# Others.net
KiCad netlist of a schematic drawn in Altium Designer
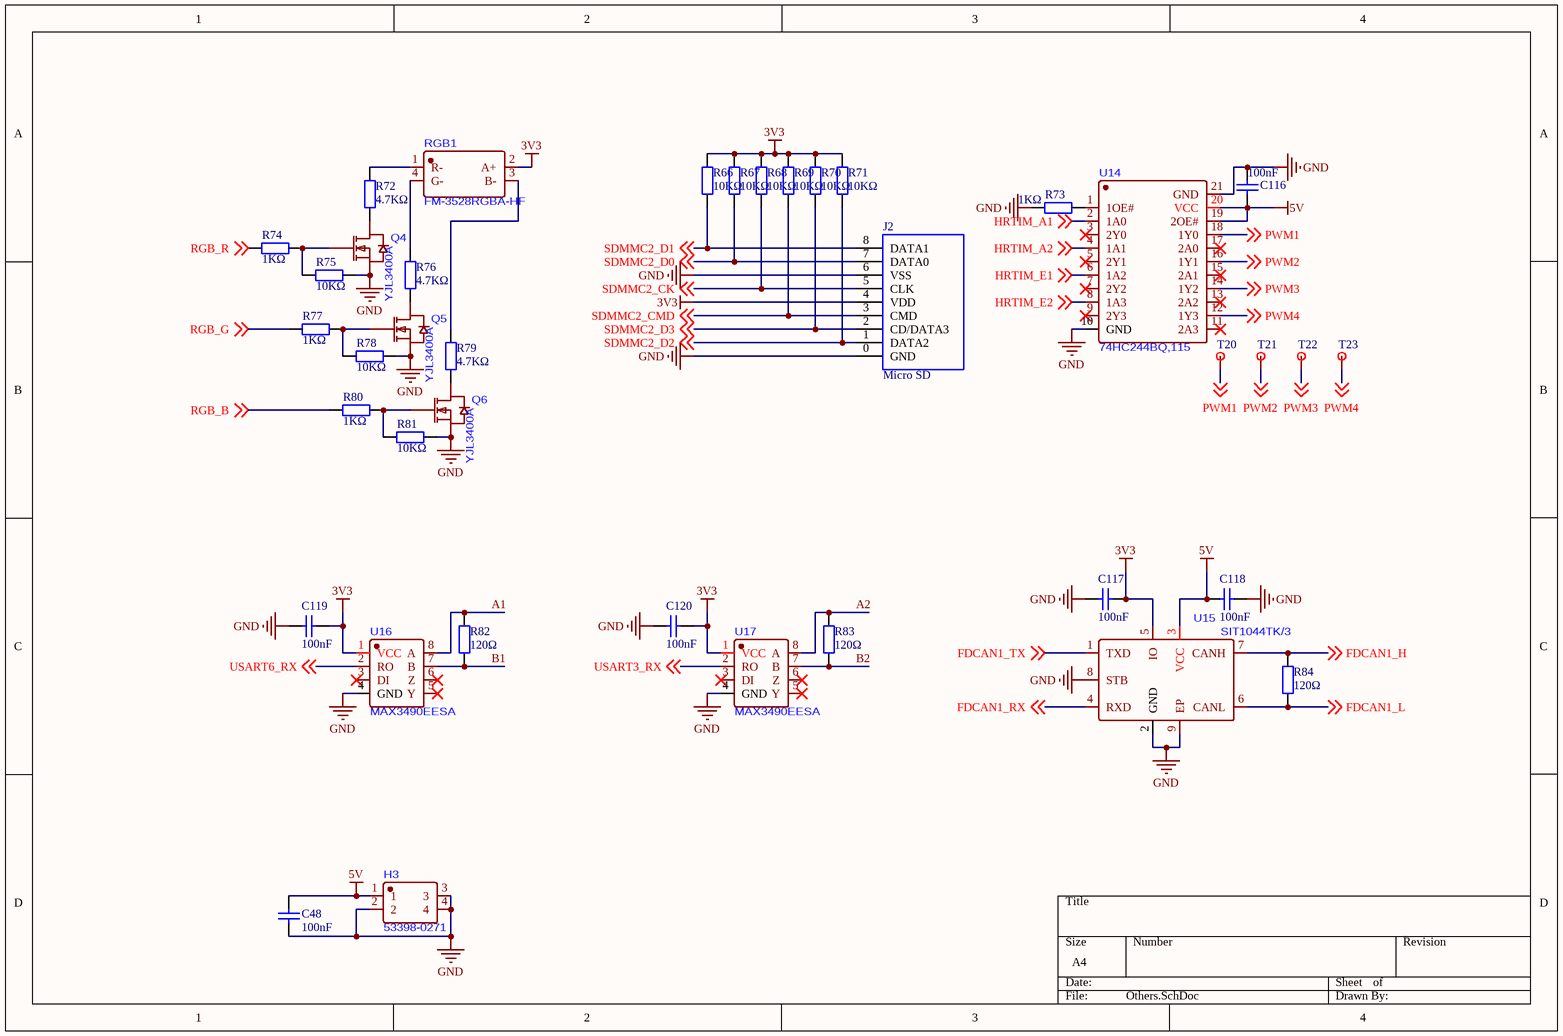
[diagram p0: Others.SchDoc]

(export (version "E")
  (design (tool "Eeschema 10.0.6"))
  (components
    (comp (ref "C48")
      (value "100nF")
      (footprint "0402_C")
      (description "贴片电容")
      (libsource (lib "Miscellaneous Devices LC") (part "0402 100nF (104) 10% 16V"))
    )
    (comp (ref "C116")
      (value "100nF")
      (footprint "0402_C")
      (description "贴片电容")
      (libsource (lib "Miscellaneous Devices LC") (part "0402 100nF (104) 10% 16V"))
    )
    (comp (ref "C117")
      (value "100nF")
      (footprint "0402_C")
      (description "贴片电容")
      (libsource (lib "Miscellaneous Devices LC") (part "0402 100nF (104) 10% 16V"))
    )
    (comp (ref "C118")
      (value "100nF")
      (footprint "0402_C")
      (description "贴片电容")
      (libsource (lib "Miscellaneous Devices LC") (part "0402 100nF (104) 10% 16V"))
    )
    (comp (ref "C119")
      (value "100nF")
      (footprint "0402_C")
      (description "贴片电容")
      (libsource (lib "Miscellaneous Devices LC") (part "0402 100nF (104) 10% 16V"))
    )
    (comp (ref "C120")
      (value "100nF")
      (footprint "0402_C")
      (description "贴片电容")
      (libsource (lib "Miscellaneous Devices LC") (part "0402 100nF (104) 10% 16V"))
    )
    (comp (ref "H3")
      (value "53398-0271")
      (footprint "CONN-SMD_2P-P1.25_53398-0271")
      (libsource (lib "JiangCi") (part "53398-0271"))
    )
    (comp (ref "J2")
      (value "Micro SD")
      (footprint "SD卡座短")
      (description "Micro SD卡")
      (fields (field (name "版权归属") "黎明电子style"))
      (libsource (lib "RM2020原理图库v1.3 (1)") (part "SD卡 短"))
    )
    (comp (ref "Q4")
      (value "YJL3400A")
      (footprint "SOT-23-3_L2.9-W1.3-P1.90-LS2.4-BR")
      (libsource (lib "JiangCi") (part "YJL3400A"))
    )
    (comp (ref "Q5")
      (value "YJL3400A")
      (footprint "SOT-23-3_L2.9-W1.3-P1.90-LS2.4-BR")
      (libsource (lib "JiangCi") (part "YJL3400A"))
    )
    (comp (ref "Q6")
      (value "YJL3400A")
      (footprint "SOT-23-3_L2.9-W1.3-P1.90-LS2.4-BR")
      (libsource (lib "JiangCi") (part "YJL3400A"))
    )
    (comp (ref "R66")
      (value "10KΩ")
      (footprint "0402_R")
      (description "贴片电阻")
      (libsource (lib "Miscellaneous Devices LC") (part "0402 10KΩ (1002) 1%"))
    )
    (comp (ref "R67")
      (value "10KΩ")
      (footprint "0402_R")
      (description "贴片电阻")
      (libsource (lib "Miscellaneous Devices LC") (part "0402 10KΩ (1002) 1%"))
    )
    (comp (ref "R68")
      (value "10KΩ")
      (footprint "0402_R")
      (description "贴片电阻")
      (libsource (lib "Miscellaneous Devices LC") (part "0402 10KΩ (1002) 1%"))
    )
    (comp (ref "R69")
      (value "10KΩ")
      (footprint "0402_R")
      (description "贴片电阻")
      (libsource (lib "Miscellaneous Devices LC") (part "0402 10KΩ (1002) 1%"))
    )
    (comp (ref "R70")
      (value "10KΩ")
      (footprint "0402_R")
      (description "贴片电阻")
      (libsource (lib "Miscellaneous Devices LC") (part "0402 10KΩ (1002) 1%"))
    )
    (comp (ref "R71")
      (value "10KΩ")
      (footprint "0402_R")
      (description "贴片电阻")
      (libsource (lib "Miscellaneous Devices LC") (part "0402 10KΩ (1002) 1%"))
    )
    (comp (ref "R72")
      (value "4.7KΩ")
      (footprint "0402_R")
      (description "贴片电阻")
      (libsource (lib "Miscellaneous Devices LC") (part "0402 10KΩ (1002) 1%"))
    )
    (comp (ref "R73")
      (value "1KΩ")
      (footprint "0402_R")
      (description "贴片电阻")
      (libsource (lib "") (part "0402 10KΩ (1002) 1%_1"))
    )
    (comp (ref "R74")
      (value "1KΩ")
      (footprint "0402_R")
      (description "贴片电阻")
      (libsource (lib "") (part "0402 10KΩ (1002) 1%_1"))
    )
    (comp (ref "R75")
      (value "10KΩ")
      (footprint "0402_R")
      (description "贴片电阻")
      (libsource (lib "") (part "0402 10KΩ (1002) 1%_1"))
    )
    (comp (ref "R76")
      (value "4.7KΩ")
      (footprint "0402_R")
      (description "贴片电阻")
      (libsource (lib "Miscellaneous Devices LC") (part "0402 10KΩ (1002) 1%"))
    )
    (comp (ref "R77")
      (value "1KΩ")
      (footprint "0402_R")
      (description "贴片电阻")
      (libsource (lib "") (part "0402 10KΩ (1002) 1%_1"))
    )
    (comp (ref "R78")
      (value "10KΩ")
      (footprint "0402_R")
      (description "贴片电阻")
      (libsource (lib "") (part "0402 10KΩ (1002) 1%_1"))
    )
    (comp (ref "R79")
      (value "4.7KΩ")
      (footprint "0402_R")
      (description "贴片电阻")
      (libsource (lib "Miscellaneous Devices LC") (part "0402 10KΩ (1002) 1%"))
    )
    (comp (ref "R80")
      (value "1KΩ")
      (footprint "0402_R")
      (description "贴片电阻")
      (libsource (lib "") (part "0402 10KΩ (1002) 1%_1"))
    )
    (comp (ref "R81")
      (value "10KΩ")
      (footprint "0402_R")
      (description "贴片电阻")
      (libsource (lib "") (part "0402 10KΩ (1002) 1%_1"))
    )
    (comp (ref "R82")
      (value "120Ω")
      (footprint "0402_R")
      (description "贴片电阻")
      (libsource (lib "Miscellaneous Devices LC") (part "0402 120Ω (1200) 1%"))
    )
    (comp (ref "R83")
      (value "120Ω")
      (footprint "0402_R")
      (description "贴片电阻")
      (libsource (lib "Miscellaneous Devices LC") (part "0402 120Ω (1200) 1%"))
    )
    (comp (ref "R84")
      (value "120Ω")
      (footprint "0402_R")
      (description "贴片电阻")
      (libsource (lib "Miscellaneous Devices LC") (part "0402 120Ω (1200) 1%"))
    )
    (comp (ref "RGB1")
      (value "FM-3528RGBA-HF")
      (footprint "LED-SMD_4P-L3.2-W2.8-LS3.5-BR-1")
      (libsource (lib "JiangCi") (part "FM-3528RGBA-HF"))
    )
    (comp (ref "T20")
      (value "testpoint")
      (footprint "testpoint")
      (libsource (lib "JiangCi") (part "testpoint"))
    )
    (comp (ref "T21")
      (value "testpoint")
      (footprint "testpoint")
      (libsource (lib "JiangCi") (part "testpoint"))
    )
    (comp (ref "T22")
      (value "testpoint")
      (footprint "testpoint")
      (libsource (lib "JiangCi") (part "testpoint"))
    )
    (comp (ref "T23")
      (value "testpoint")
      (footprint "testpoint")
      (libsource (lib "JiangCi") (part "testpoint"))
    )
    (comp (ref "U14")
      (value "74HC244BQ,115")
      (footprint "DHVQFN20_L4.5-W2.5-P0.50-BL-EP")
      (libsource (lib "JiangCi") (part "74HC244BQ,115"))
    )
    (comp (ref "U15")
      (value "SIT1044TK/3")
      (footprint "TDFN-8_L3.0-W3.0-P0.65-BL-EP")
      (libsource (lib "VeryNB_H750") (part "SIT1044TK/3"))
    )
    (comp (ref "U16")
      (value "MAX3490EESA")
      (footprint "SOIC-8_L4.9-W3.9-P1.27-LS6.0-BL")
      (libsource (lib "JiangCi") (part "MAX3490EESA"))
    )
    (comp (ref "U17")
      (value "MAX3490EESA")
      (footprint "SOIC-8_L4.9-W3.9-P1.27-LS6.0-BL")
      (libsource (lib "JiangCi") (part "MAX3490EESA"))
    )
  )
  (nets
    (net (code "1") (name "/A1") (class "Default")
      (node (ref "R82") (pin "2") (pinfunction "2_2") (pintype "passive"))
      (node (ref "U16") (pin "8") (pinfunction "A_8") (pintype "passive"))
    )
    (net (code "2") (name "/A2") (class "Default")
      (node (ref "R83") (pin "2") (pinfunction "2_2") (pintype "passive"))
      (node (ref "U17") (pin "8") (pinfunction "A_8") (pintype "passive"))
    )
    (net (code "3") (name "/B1") (class "Default")
      (node (ref "R82") (pin "1") (pinfunction "1_1") (pintype "passive"))
      (node (ref "U16") (pin "7") (pinfunction "B_7") (pintype "passive"))
    )
    (net (code "4") (name "/B2") (class "Default")
      (node (ref "R83") (pin "1") (pinfunction "1_1") (pintype "passive"))
      (node (ref "U17") (pin "7") (pinfunction "B_7") (pintype "passive"))
    )
    (net (code "5") (name "3V3") (class "Default")
      (node (ref "C117") (pin "1") (pinfunction "1_1") (pintype "passive"))
      (node (ref "C119") (pin "1") (pinfunction "1_1") (pintype "passive"))
      (node (ref "C120") (pin "1") (pinfunction "1_1") (pintype "passive"))
      (node (ref "J2") (pin "4") (pinfunction "VDD_4") (pintype "passive"))
      (node (ref "R66") (pin "2") (pinfunction "2_2") (pintype "passive"))
      (node (ref "R67") (pin "2") (pinfunction "2_2") (pintype "passive"))
      (node (ref "R68") (pin "2") (pinfunction "2_2") (pintype "passive"))
      (node (ref "R69") (pin "2") (pinfunction "2_2") (pintype "passive"))
      (node (ref "R70") (pin "2") (pinfunction "2_2") (pintype "passive"))
      (node (ref "R71") (pin "2") (pinfunction "2_2") (pintype "passive"))
      (node (ref "RGB1") (pin "2") (pinfunction "A+_2") (pintype "passive"))
      (node (ref "U15") (pin "5") (pinfunction "IO_5") (pintype "passive"))
      (node (ref "U16") (pin "1") (pinfunction "VCC_1") (pintype "passive"))
      (node (ref "U17") (pin "1") (pinfunction "VCC_1") (pintype "passive"))
    )
    (net (code "6") (name "5V") (class "Default")
      (node (ref "C116") (pin "1") (pinfunction "1_1") (pintype "passive"))
      (node (ref "C118") (pin "2") (pinfunction "2_2") (pintype "passive"))
      (node (ref "C48") (pin "1") (pinfunction "1_1") (pintype "passive"))
      (node (ref "H3") (pin "1") (pinfunction "1_1") (pintype "passive"))
      (node (ref "U14") (pin "19") (pinfunction "2OE#_19") (pintype "passive"))
      (node (ref "U14") (pin "20") (pinfunction "VCC_20") (pintype "passive"))
      (node (ref "U15") (pin "3") (pinfunction "VCC_3") (pintype "passive"))
    )
    (net (code "7") (name "FDCAN1_H") (class "Default")
      (node (ref "R84") (pin "2") (pinfunction "2_2") (pintype "passive"))
      (node (ref "U15") (pin "7") (pinfunction "CANH_7") (pintype "passive"))
    )
    (net (code "8") (name "FDCAN1_L") (class "Default")
      (node (ref "R84") (pin "1") (pinfunction "1_1") (pintype "passive"))
      (node (ref "U15") (pin "6") (pinfunction "CANL_6") (pintype "passive"))
    )
    (net (code "9") (name "FDCAN1_RX") (class "Default")
      (node (ref "U15") (pin "4") (pinfunction "RXD_4") (pintype "passive"))
    )
    (net (code "10") (name "FDCAN1_TX") (class "Default")
      (node (ref "U15") (pin "1") (pinfunction "TXD_1") (pintype "passive"))
    )
    (net (code "11") (name "GND") (class "Default")
      (node (ref "C116") (pin "2") (pinfunction "2_2") (pintype "passive"))
      (node (ref "C117") (pin "2") (pinfunction "2_2") (pintype "passive"))
      (node (ref "C118") (pin "1") (pinfunction "1_1") (pintype "passive"))
      (node (ref "C119") (pin "2") (pinfunction "2_2") (pintype "passive"))
      (node (ref "C120") (pin "2") (pinfunction "2_2") (pintype "passive"))
      (node (ref "C48") (pin "2") (pinfunction "2_2") (pintype "passive"))
      (node (ref "H3") (pin "2") (pinfunction "2_2") (pintype "passive"))
      (node (ref "H3") (pin "3") (pinfunction "3_3") (pintype "passive"))
      (node (ref "H3") (pin "4") (pinfunction "4_4") (pintype "passive"))
      (node (ref "J2") (pin "0") (pinfunction "GND_0") (pintype "passive"))
      (node (ref "J2") (pin "6") (pinfunction "VSS_6") (pintype "passive"))
      (node (ref "Q4") (pin "2") (pinfunction "S_2") (pintype "passive"))
      (node (ref "Q5") (pin "2") (pinfunction "S_2") (pintype "passive"))
      (node (ref "Q6") (pin "2") (pinfunction "S_2") (pintype "passive"))
      (node (ref "R73") (pin "1") (pinfunction "1_1") (pintype "passive"))
      (node (ref "R75") (pin "2") (pinfunction "2_2") (pintype "passive"))
      (node (ref "R78") (pin "2") (pinfunction "2_2") (pintype "passive"))
      (node (ref "R81") (pin "2") (pinfunction "2_2") (pintype "passive"))
      (node (ref "U14") (pin "10") (pinfunction "GND_10") (pintype "passive"))
      (node (ref "U14") (pin "21") (pinfunction "GND_21") (pintype "passive"))
      (node (ref "U15") (pin "2") (pinfunction "GND_2") (pintype "passive"))
      (node (ref "U15") (pin "8") (pinfunction "STB_8") (pintype "passive"))
      (node (ref "U15") (pin "9") (pinfunction "EP_9") (pintype "passive"))
      (node (ref "U16") (pin "4") (pinfunction "GND_4") (pintype "passive"))
      (node (ref "U17") (pin "4") (pinfunction "GND_4") (pintype "passive"))
    )
    (net (code "12") (name "HRTIM_A1") (class "Default")
      (node (ref "U14") (pin "2") (pinfunction "1A0_2") (pintype "passive"))
    )
    (net (code "13") (name "HRTIM_A2") (class "Default")
      (node (ref "U14") (pin "4") (pinfunction "1A1_4") (pintype "passive"))
    )
    (net (code "14") (name "HRTIM_E1") (class "Default")
      (node (ref "U14") (pin "6") (pinfunction "1A2_6") (pintype "passive"))
    )
    (net (code "15") (name "HRTIM_E2") (class "Default")
      (node (ref "U14") (pin "8") (pinfunction "1A3_8") (pintype "passive"))
    )
    (net (code "16") (name "Net-(Q4-D)") (class "Default")
      (node (ref "Q4") (pin "3") (pinfunction "D_3") (pintype "passive"))
      (node (ref "R72") (pin "1") (pinfunction "1_1") (pintype "passive"))
    )
    (net (code "17") (name "Net-(Q4-G)") (class "Default")
      (node (ref "Q4") (pin "1") (pinfunction "G_1") (pintype "passive"))
      (node (ref "R74") (pin "2") (pinfunction "2_2") (pintype "passive"))
      (node (ref "R75") (pin "1") (pinfunction "1_1") (pintype "passive"))
    )
    (net (code "18") (name "Net-(Q5-D)") (class "Default")
      (node (ref "Q5") (pin "3") (pinfunction "D_3") (pintype "passive"))
      (node (ref "R76") (pin "1") (pinfunction "1_1") (pintype "passive"))
    )
    (net (code "19") (name "Net-(Q5-G)") (class "Default")
      (node (ref "Q5") (pin "1") (pinfunction "G_1") (pintype "passive"))
      (node (ref "R77") (pin "2") (pinfunction "2_2") (pintype "passive"))
      (node (ref "R78") (pin "1") (pinfunction "1_1") (pintype "passive"))
    )
    (net (code "20") (name "Net-(Q6-D)") (class "Default")
      (node (ref "Q6") (pin "3") (pinfunction "D_3") (pintype "passive"))
      (node (ref "R79") (pin "1") (pinfunction "1_1") (pintype "passive"))
    )
    (net (code "21") (name "Net-(Q6-G)") (class "Default")
      (node (ref "Q6") (pin "1") (pinfunction "G_1") (pintype "passive"))
      (node (ref "R80") (pin "2") (pinfunction "2_2") (pintype "passive"))
      (node (ref "R81") (pin "1") (pinfunction "1_1") (pintype "passive"))
    )
    (net (code "22") (name "Net-(RGB1-B-)") (class "Default")
      (node (ref "R79") (pin "2") (pinfunction "2_2") (pintype "passive"))
      (node (ref "RGB1") (pin "3") (pinfunction "B-_3") (pintype "passive"))
    )
    (net (code "23") (name "Net-(RGB1-G-)") (class "Default")
      (node (ref "R76") (pin "2") (pinfunction "2_2") (pintype "passive"))
      (node (ref "RGB1") (pin "4") (pinfunction "G-_4") (pintype "passive"))
    )
    (net (code "24") (name "Net-(RGB1-R-)") (class "Default")
      (node (ref "R72") (pin "2") (pinfunction "2_2") (pintype "passive"))
      (node (ref "RGB1") (pin "1") (pinfunction "R-_1") (pintype "passive"))
    )
    (net (code "25") (name "Net-(U14-1OE#)") (class "Default")
      (node (ref "R73") (pin "2") (pinfunction "2_2") (pintype "passive"))
      (node (ref "U14") (pin "1") (pinfunction "1OE#_1") (pintype "passive"))
    )
    (net (code "26") (name "PWM1") (class "Default")
      (node (ref "T20") (pin "1") (pinfunction "R_1") (pintype "passive"))
      (node (ref "U14") (pin "18") (pinfunction "1Y0_18") (pintype "passive"))
    )
    (net (code "27") (name "PWM2") (class "Default")
      (node (ref "T21") (pin "1") (pinfunction "R_1") (pintype "passive"))
      (node (ref "U14") (pin "16") (pinfunction "1Y1_16") (pintype "passive"))
    )
    (net (code "28") (name "PWM3") (class "Default")
      (node (ref "T22") (pin "1") (pinfunction "R_1") (pintype "passive"))
      (node (ref "U14") (pin "14") (pinfunction "1Y2_14") (pintype "passive"))
    )
    (net (code "29") (name "PWM4") (class "Default")
      (node (ref "T23") (pin "1") (pinfunction "R_1") (pintype "passive"))
      (node (ref "U14") (pin "12") (pinfunction "1Y3_12") (pintype "passive"))
    )
    (net (code "30") (name "RGB_B") (class "Default")
      (node (ref "R80") (pin "1") (pinfunction "1_1") (pintype "passive"))
    )
    (net (code "31") (name "RGB_G") (class "Default")
      (node (ref "R77") (pin "1") (pinfunction "1_1") (pintype "passive"))
    )
    (net (code "32") (name "RGB_R") (class "Default")
      (node (ref "R74") (pin "1") (pinfunction "1_1") (pintype "passive"))
    )
    (net (code "33") (name "SDMMC2_CK") (class "Default")
      (node (ref "J2") (pin "5") (pinfunction "CLK_5") (pintype "passive"))
      (node (ref "R68") (pin "1") (pinfunction "1_1") (pintype "passive"))
    )
    (net (code "34") (name "SDMMC2_CMD") (class "Default")
      (node (ref "J2") (pin "3") (pinfunction "CMD_3") (pintype "passive"))
      (node (ref "R69") (pin "1") (pinfunction "1_1") (pintype "passive"))
    )
    (net (code "35") (name "SDMMC2_D0") (class "Default")
      (node (ref "J2") (pin "7") (pinfunction "DATA0_7") (pintype "passive"))
      (node (ref "R67") (pin "1") (pinfunction "1_1") (pintype "passive"))
    )
    (net (code "36") (name "SDMMC2_D1") (class "Default")
      (node (ref "J2") (pin "8") (pinfunction "DATA1_8") (pintype "passive"))
      (node (ref "R66") (pin "1") (pinfunction "1_1") (pintype "passive"))
    )
    (net (code "37") (name "SDMMC2_D2") (class "Default")
      (node (ref "J2") (pin "1") (pinfunction "DATA2_1") (pintype "passive"))
      (node (ref "R71") (pin "1") (pinfunction "1_1") (pintype "passive"))
    )
    (net (code "38") (name "SDMMC2_D3") (class "Default")
      (node (ref "J2") (pin "2") (pinfunction "CD/DATA3_2") (pintype "passive"))
      (node (ref "R70") (pin "1") (pinfunction "1_1") (pintype "passive"))
    )
    (net (code "39") (name "USART3_RX") (class "Default")
      (node (ref "U17") (pin "2") (pinfunction "RO_2") (pintype "passive"))
    )
    (net (code "40") (name "USART6_RX") (class "Default")
      (node (ref "U16") (pin "2") (pinfunction "RO_2") (pintype "passive"))
    )
    (net (code "41") (name "unconnected-(U14-2A0-Pad17)") (class "Default")
      (node (ref "U14") (pin "17") (pinfunction "2A0_17") (pintype "passive+no_connect"))
    )
    (net (code "42") (name "unconnected-(U14-2A1-Pad15)") (class "Default")
      (node (ref "U14") (pin "15") (pinfunction "2A1_15") (pintype "passive+no_connect"))
    )
    (net (code "43") (name "unconnected-(U14-2A2-Pad13)") (class "Default")
      (node (ref "U14") (pin "13") (pinfunction "2A2_13") (pintype "passive+no_connect"))
    )
    (net (code "44") (name "unconnected-(U14-2A3-Pad11)") (class "Default")
      (node (ref "U14") (pin "11") (pinfunction "2A3_11") (pintype "passive+no_connect"))
    )
    (net (code "45") (name "unconnected-(U14-2Y0-Pad3)") (class "Default")
      (node (ref "U14") (pin "3") (pinfunction "2Y0_3") (pintype "passive+no_connect"))
    )
    (net (code "46") (name "unconnected-(U14-2Y1-Pad5)") (class "Default")
      (node (ref "U14") (pin "5") (pinfunction "2Y1_5") (pintype "passive+no_connect"))
    )
    (net (code "47") (name "unconnected-(U14-2Y2-Pad7)") (class "Default")
      (node (ref "U14") (pin "7") (pinfunction "2Y2_7") (pintype "passive+no_connect"))
    )
    (net (code "48") (name "unconnected-(U14-2Y3-Pad9)") (class "Default")
      (node (ref "U14") (pin "9") (pinfunction "2Y3_9") (pintype "passive+no_connect"))
    )
    (net (code "49") (name "unconnected-(U16-DI-Pad3)") (class "Default")
      (node (ref "U16") (pin "3") (pinfunction "DI_3") (pintype "passive+no_connect"))
    )
    (net (code "50") (name "unconnected-(U16-Y-Pad5)") (class "Default")
      (node (ref "U16") (pin "5") (pinfunction "Y_5") (pintype "passive+no_connect"))
    )
    (net (code "51") (name "unconnected-(U16-Z-Pad6)") (class "Default")
      (node (ref "U16") (pin "6") (pinfunction "Z_6") (pintype "passive+no_connect"))
    )
    (net (code "52") (name "unconnected-(U17-DI-Pad3)") (class "Default")
      (node (ref "U17") (pin "3") (pinfunction "DI_3") (pintype "passive+no_connect"))
    )
    (net (code "53") (name "unconnected-(U17-Y-Pad5)") (class "Default")
      (node (ref "U17") (pin "5") (pinfunction "Y_5") (pintype "passive+no_connect"))
    )
    (net (code "54") (name "unconnected-(U17-Z-Pad6)") (class "Default")
      (node (ref "U17") (pin "6") (pinfunction "Z_6") (pintype "passive+no_connect"))
    )
  )
)
